# MCU.net
KiCad netlist of a schematic drawn in Altium Designer
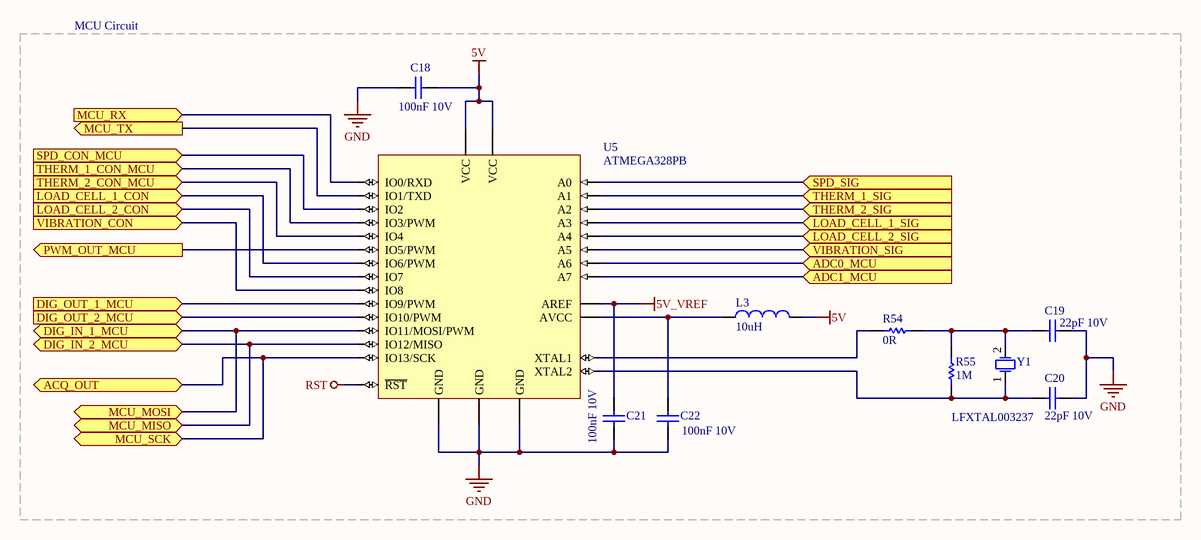
[diagram p0: MCU.SchDoc]

(export (version "E")
  (design (tool "Eeschema 10.0.6"))
  (components
    (comp (ref "C18")
      (value "100nF 10V")
      (footprint "0402")
      (description "Capacitor")
      (fields (field (name "PARTNUMBER") "CAP.100n.10V.20%.SMD.0402") (field (name "MANUFACTURER") "Wurth"))
      (libsource (lib "IntLib") (part "Cap"))
    )
    (comp (ref "C19")
      (value "22pF 10V")
      (footprint "1608[0603]")
      (description "Capacitor")
      (fields (field (name "PARTNUMBER") "CAP.22p.10V.5%.SMD.0603") (field (name "MANUFACTURER") "Wurth"))
      (libsource (lib "IntLib") (part "Cap"))
    )
    (comp (ref "C20")
      (value "22pF 10V")
      (footprint "1608[0603]")
      (description "Capacitor")
      (fields (field (name "PARTNUMBER") "CAP.22p.10V.5%.SMD.0603") (field (name "MANUFACTURER") "Wurth"))
      (libsource (lib "IntLib") (part "Cap"))
    )
    (comp (ref "C21")
      (value "100nF 10V")
      (footprint "0402")
      (description "Capacitor")
      (fields (field (name "PARTNUMBER") "CAP.100n.10V.20%.SMD.0402") (field (name "MANUFACTURER") "Wurth"))
      (libsource (lib "IntLib") (part "Cap"))
    )
    (comp (ref "C22")
      (value "100nF 10V")
      (footprint "0402")
      (description "Capacitor")
      (fields (field (name "PARTNUMBER") "CAP.100n.10V.20%.SMD.0402") (field (name "MANUFACTURER") "Wurth"))
      (libsource (lib "IntLib") (part "Cap"))
    )
    (comp (ref "L3")
      (value "10uH")
      (footprint "6-0805_M")
      (description "Chip Inductor")
      (fields (field (name "PARTNUMBER") "LBC2012T100M") (field (name "MANUFACTURER") "Taiyo Yuden"))
      (libsource (lib "IntLib") (part "Inductor"))
    )
    (comp (ref "R54")
      (value "0R")
      (footprint "6-0805_M")
      (description "Resistor")
      (fields (field (name "PARTNUMBER") "RES.0R.1/8W.5%.SMD.0805") (field (name "MANUFACTURER") "Vishay"))
      (libsource (lib "IntLib") (part "Res"))
    )
    (comp (ref "R55")
      (value "1M")
      (footprint "6-0805_M")
      (description "Resistor")
      (fields (field (name "PARTNUMBER") "RES.1M.1/8W.5%.SMD.0805") (field (name "MANUFACTURER") "Bourns"))
      (libsource (lib "IntLib") (part "Res"))
    )
    (comp (ref "U5")
      (value "ATMEGA328PB")
      (footprint "QFP80P900X900X120-32N")
      (description "8-bit AVR® RISC-based microcontroller (MCU) with picoPower® technology.")
      (fields (field (name "MANUFACTURER") "Microchip"))
      (libsource (lib "IntLib") (part "ATMEGA328PB-AU"))
    )
    (comp (ref "Y1")
      (value "LFXTAL003237")
      (footprint "HC49/4HSMX")
      (description "Crystals 16.0MHz 13.4 x 4.9 x 4.3mm")
      (fields (field (name "MANUFACTURER") "IQD"))
      (libsource (lib "IntLib") (part "LFXTAL003237"))
    )
  )
  (nets
    (net (code "1") (name "/ACQ_OUT") (class "Default")
      (node (ref "U5") (pin "17") (pinfunction "IO13/SCK_17") (pintype "bidirectional"))
    )
    (net (code "2") (name "/ADC0_MCU") (class "Default")
      (node (ref "U5") (pin "19") (pinfunction "A6_19") (pintype "input"))
    )
    (net (code "3") (name "/ADC1_MCU") (class "Default")
      (node (ref "U5") (pin "22") (pinfunction "A7_22") (pintype "input"))
    )
    (net (code "4") (name "/DIG_IN_1_MCU") (class "Default")
      (node (ref "U5") (pin "15") (pinfunction "IO11/MOSI/PWM_15") (pintype "bidirectional"))
    )
    (net (code "5") (name "/DIG_IN_2_MCU") (class "Default")
      (node (ref "U5") (pin "16") (pinfunction "IO12/MISO_16") (pintype "bidirectional"))
    )
    (net (code "6") (name "/DIG_OUT_1_MCU") (class "Default")
      (node (ref "U5") (pin "13") (pinfunction "IO9/PWM_13") (pintype "bidirectional"))
    )
    (net (code "7") (name "/DIG_OUT_2_MCU") (class "Default")
      (node (ref "U5") (pin "14") (pinfunction "IO10/PWM_14") (pintype "bidirectional"))
    )
    (net (code "8") (name "/LOAD_CELL_1_CON") (class "Default")
      (node (ref "U5") (pin "10") (pinfunction "IO6/PWM_10") (pintype "bidirectional"))
    )
    (net (code "9") (name "/LOAD_CELL_1_SIG") (class "Default")
      (node (ref "U5") (pin "26") (pinfunction "A3_26") (pintype "input"))
    )
    (net (code "10") (name "/LOAD_CELL_2_CON") (class "Default")
      (node (ref "U5") (pin "11") (pinfunction "IO7_11") (pintype "bidirectional"))
    )
    (net (code "11") (name "/LOAD_CELL_2_SIG") (class "Default")
      (node (ref "U5") (pin "27") (pinfunction "A4_27") (pintype "input"))
    )
    (net (code "12") (name "/MCU_RX") (class "Default")
      (node (ref "U5") (pin "30") (pinfunction "IO0/RXD_30") (pintype "bidirectional"))
    )
    (net (code "13") (name "/MCU_TX") (class "Default")
      (node (ref "U5") (pin "31") (pinfunction "IO1/TXD_31") (pintype "bidirectional"))
    )
    (net (code "14") (name "/PWM_OUT_MCU") (class "Default")
      (node (ref "U5") (pin "9") (pinfunction "IO5/PWM_9") (pintype "bidirectional"))
    )
    (net (code "15") (name "/SPD_CON_MCU") (class "Default")
      (node (ref "U5") (pin "32") (pinfunction "IO2_32") (pintype "bidirectional"))
    )
    (net (code "16") (name "/SPD_SIG") (class "Default")
      (node (ref "U5") (pin "23") (pinfunction "A0_23") (pintype "input"))
    )
    (net (code "17") (name "/THERM_1_CON_MCU") (class "Default")
      (node (ref "U5") (pin "1") (pinfunction "IO3/PWM_1") (pintype "bidirectional"))
    )
    (net (code "18") (name "/THERM_1_SIG") (class "Default")
      (node (ref "U5") (pin "24") (pinfunction "A1_24") (pintype "input"))
    )
    (net (code "19") (name "/THERM_2_CON_MCU") (class "Default")
      (node (ref "U5") (pin "2") (pinfunction "IO4_2") (pintype "bidirectional"))
    )
    (net (code "20") (name "/THERM_2_SIG") (class "Default")
      (node (ref "U5") (pin "25") (pinfunction "A2_25") (pintype "input"))
    )
    (net (code "21") (name "/VIBRATION_CON") (class "Default")
      (node (ref "U5") (pin "12") (pinfunction "IO8_12") (pintype "bidirectional"))
    )
    (net (code "22") (name "/VIBRATION_SIG") (class "Default")
      (node (ref "U5") (pin "28") (pinfunction "A5_28") (pintype "input"))
    )
    (net (code "23") (name "5V") (class "Default")
      (node (ref "C18") (pin "2") (pinfunction "2_2") (pintype "passive"))
      (node (ref "L3") (pin "2") (pinfunction "2_2") (pintype "passive"))
      (node (ref "U5") (pin "4") (pinfunction "VCC_4") (pintype "power_in"))
      (node (ref "U5") (pin "6") (pinfunction "VCC_6") (pintype "power_in"))
    )
    (net (code "24") (name "5V_VREF") (class "Default")
      (node (ref "C21") (pin "2") (pinfunction "2_2") (pintype "passive"))
      (node (ref "U5") (pin "20") (pinfunction "AREF_20") (pintype "power_in"))
    )
    (net (code "25") (name "GND") (class "Default")
      (node (ref "C18") (pin "1") (pinfunction "1_1") (pintype "passive"))
      (node (ref "C19") (pin "2") (pinfunction "2_2") (pintype "passive"))
      (node (ref "C20") (pin "2") (pinfunction "2_2") (pintype "passive"))
      (node (ref "C21") (pin "1") (pinfunction "1_1") (pintype "passive"))
      (node (ref "C22") (pin "1") (pinfunction "1_1") (pintype "passive"))
      (node (ref "U5") (pin "21") (pinfunction "GND_21") (pintype "power_in"))
      (node (ref "U5") (pin "3") (pinfunction "GND_3") (pintype "power_in"))
      (node (ref "U5") (pin "5") (pinfunction "GND_5") (pintype "power_in"))
    )
    (net (code "26") (name "Net-(U5-AVCC)") (class "Default")
      (node (ref "C22") (pin "2") (pinfunction "2_2") (pintype "passive"))
      (node (ref "L3") (pin "1") (pinfunction "1_1") (pintype "passive"))
      (node (ref "U5") (pin "18") (pinfunction "AVCC_18") (pintype "power_in"))
    )
    (net (code "27") (name "Net-(U5-XTAL1)") (class "Default")
      (node (ref "R54") (pin "1") (pinfunction "1_1") (pintype "passive"))
      (node (ref "U5") (pin "7") (pinfunction "XTAL1_7") (pintype "bidirectional"))
    )
    (net (code "28") (name "Net-(U5-XTAL2)") (class "Default")
      (node (ref "C20") (pin "1") (pinfunction "1_1") (pintype "passive"))
      (node (ref "R55") (pin "2") (pinfunction "2_2") (pintype "passive"))
      (node (ref "U5") (pin "8") (pinfunction "XTAL2_8") (pintype "bidirectional"))
      (node (ref "Y1") (pin "1") (pinfunction "OSC1_1") (pintype "passive"))
    )
    (net (code "29") (name "Net-(Y1-OSC2)") (class "Default")
      (node (ref "C19") (pin "1") (pinfunction "1_1") (pintype "passive"))
      (node (ref "R54") (pin "2") (pinfunction "2_2") (pintype "passive"))
      (node (ref "R55") (pin "1") (pinfunction "1_1") (pintype "passive"))
      (node (ref "Y1") (pin "2") (pinfunction "OSC2_2") (pintype "passive"))
    )
    (net (code "30") (name "RST") (class "Default")
      (node (ref "U5") (pin "29") (pinfunction "~{RST}_29") (pintype "bidirectional"))
    )
  )
)
